# motoko_4_0.net
KiCad netlist of a schematic drawn in EAGLE
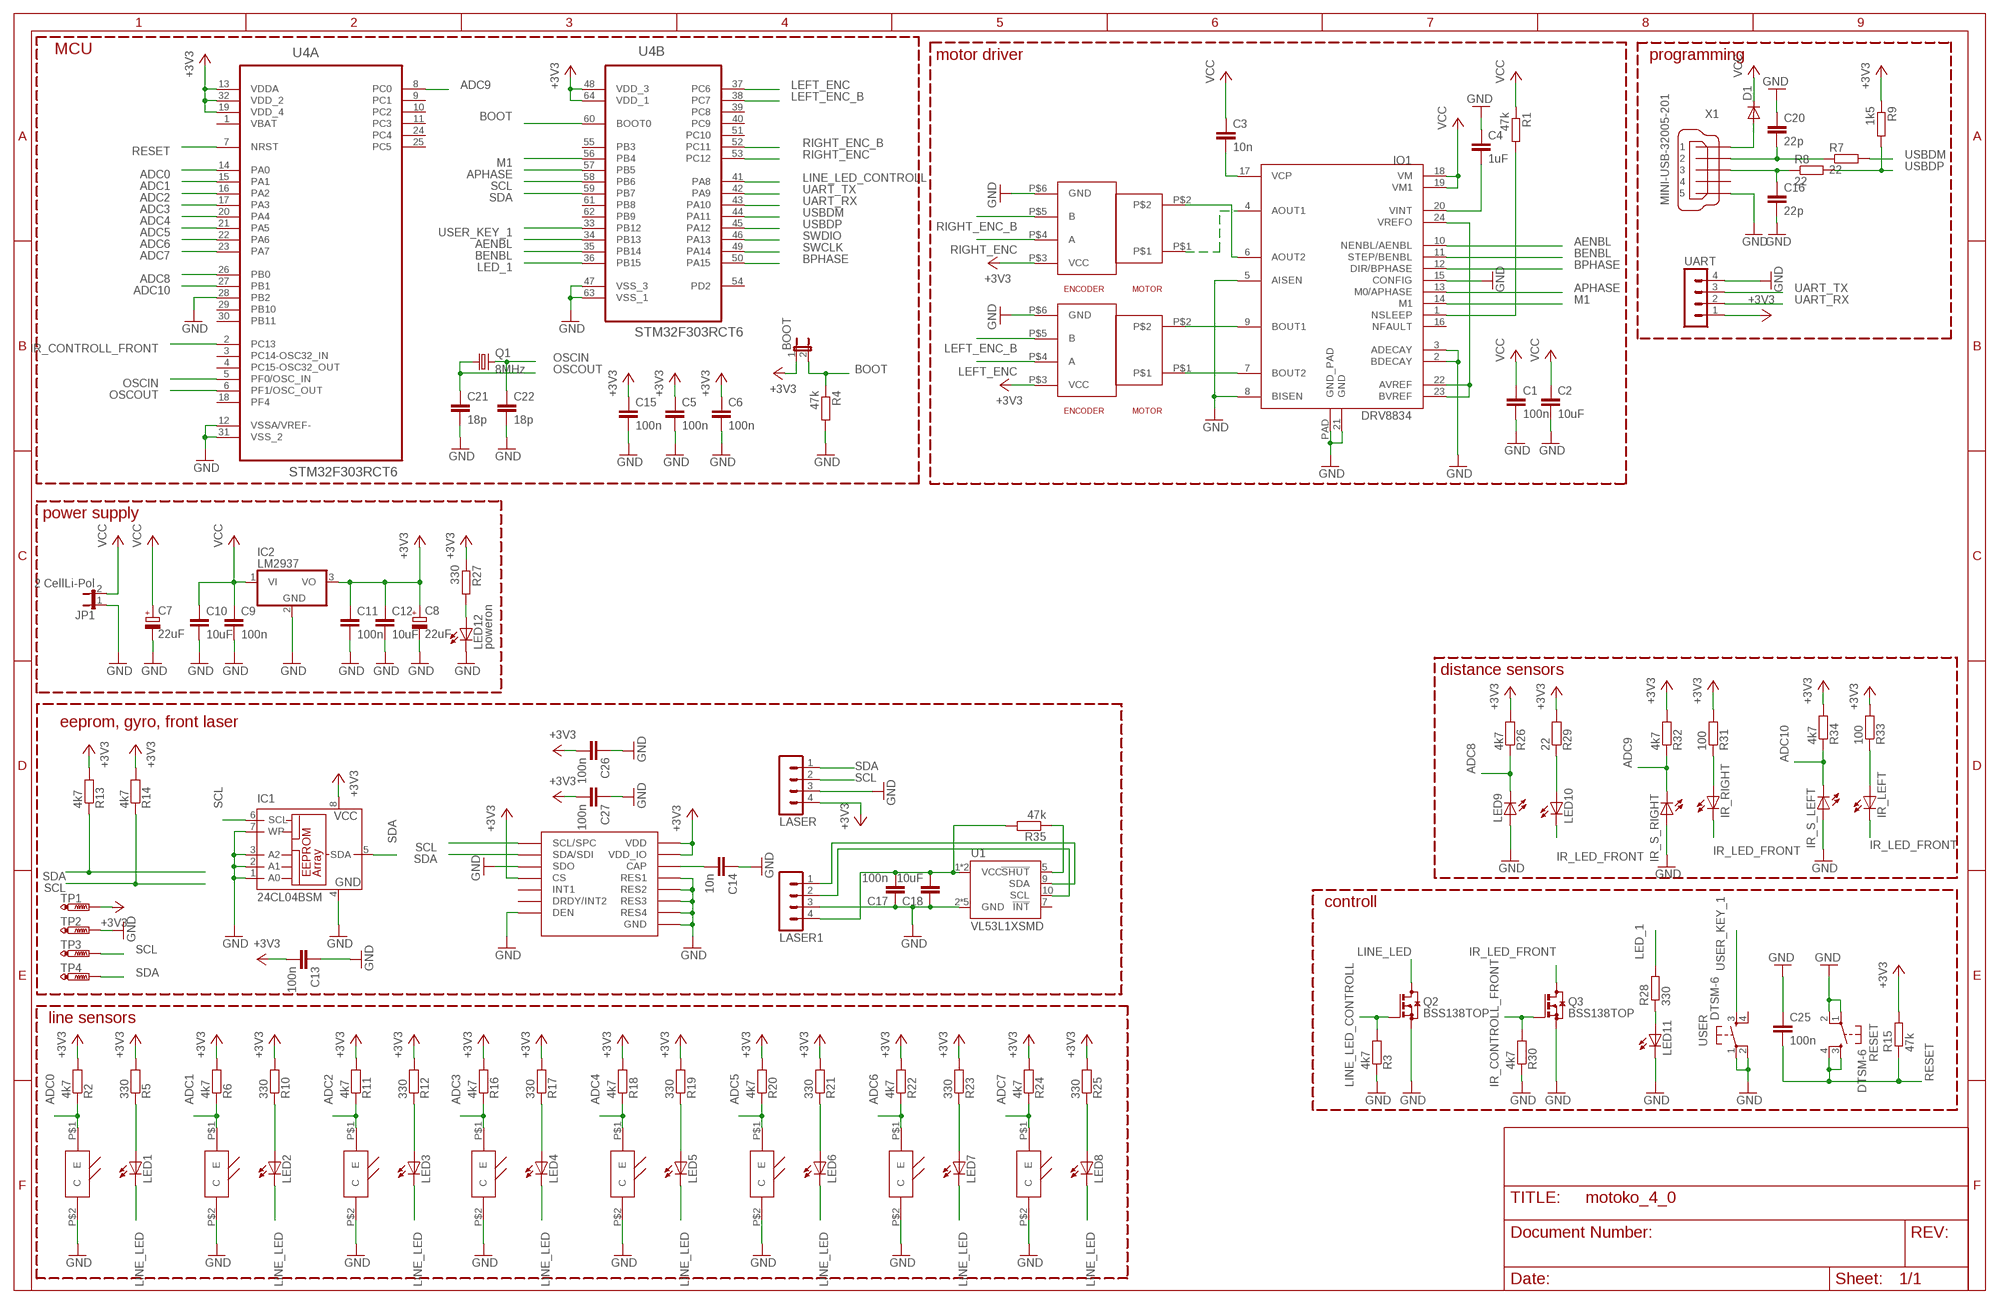
[diagram p0: schematic, sheet 1]

(export (version "E")
  (design (tool "Eeschema 10.0.6"))
  (components
    (comp (ref "BOOT")
      (value "JP1E")
      (footprint "eagle-import:JP1")
      (libsource (lib "eagle-import") (part "JP1E"))
    )
    (comp (ref "C1")
      (value "100n")
      (footprint "eagle-import:C1206")
      (libsource (lib "eagle-import") (part "C-EUC1206"))
    )
    (comp (ref "C2")
      (value "10uF")
      (footprint "eagle-import:C1206")
      (libsource (lib "eagle-import") (part "C-EUC1206"))
    )
    (comp (ref "C3")
      (value "10n")
      (footprint "eagle-import:C1206")
      (libsource (lib "eagle-import") (part "C-EUC1206"))
    )
    (comp (ref "C4")
      (value "1uF")
      (footprint "eagle-import:C1206")
      (libsource (lib "eagle-import") (part "C-EUC1206"))
    )
    (comp (ref "C5")
      (value "100n")
      (footprint "eagle-import:C0805")
      (libsource (lib "eagle-import") (part "C-EUC0805"))
    )
    (comp (ref "C6")
      (value "100n")
      (footprint "eagle-import:C0805")
      (libsource (lib "eagle-import") (part "C-EUC0805"))
    )
    (comp (ref "C7")
      (value "22uF")
      (footprint "eagle-import:153CLV-0505")
      (libsource (lib "eagle-import") (part "CPOL-EU153CLV-0505"))
    )
    (comp (ref "C8")
      (value "22uF")
      (footprint "eagle-import:153CLV-0505")
      (libsource (lib "eagle-import") (part "CPOL-EU153CLV-0505"))
    )
    (comp (ref "C9")
      (value "100n")
      (footprint "eagle-import:C0805")
      (libsource (lib "eagle-import") (part "C-EUC0805"))
    )
    (comp (ref "C10")
      (value "10uF")
      (footprint "eagle-import:C0805")
      (libsource (lib "eagle-import") (part "C-EUC0805"))
    )
    (comp (ref "C11")
      (value "100n")
      (footprint "eagle-import:C0805")
      (libsource (lib "eagle-import") (part "C-EUC0805"))
    )
    (comp (ref "C12")
      (value "10uF")
      (footprint "eagle-import:C0805")
      (libsource (lib "eagle-import") (part "C-EUC0805"))
    )
    (comp (ref "C13")
      (value "100n")
      (footprint "eagle-import:C0805")
      (libsource (lib "eagle-import") (part "C-EUC0805"))
    )
    (comp (ref "C14")
      (value "10n")
      (footprint "eagle-import:C0805")
      (libsource (lib "eagle-import") (part "C-EUC0805"))
    )
    (comp (ref "C15")
      (value "100n")
      (footprint "eagle-import:C0805")
      (libsource (lib "eagle-import") (part "C-EUC0805"))
    )
    (comp (ref "C16")
      (value "22p")
      (footprint "eagle-import:C0805")
      (libsource (lib "eagle-import") (part "C-EUC0805"))
    )
    (comp (ref "C17")
      (value "100n")
      (footprint "eagle-import:C0805")
      (libsource (lib "eagle-import") (part "C-EUC0805"))
    )
    (comp (ref "C18")
      (value "10uF")
      (footprint "eagle-import:C0805")
      (libsource (lib "eagle-import") (part "C-EUC0805"))
    )
    (comp (ref "C20")
      (value "22p")
      (footprint "eagle-import:C0805")
      (libsource (lib "eagle-import") (part "C-EUC0805"))
    )
    (comp (ref "C21")
      (value "18p")
      (footprint "eagle-import:C0805")
      (libsource (lib "eagle-import") (part "C-EUC0805"))
    )
    (comp (ref "C22")
      (value "18p")
      (footprint "eagle-import:C0805")
      (libsource (lib "eagle-import") (part "C-EUC0805"))
    )
    (comp (ref "C25")
      (value "100n")
      (footprint "eagle-import:C0805")
      (libsource (lib "eagle-import") (part "C-EUC0805"))
    )
    (comp (ref "C26")
      (value "100n")
      (footprint "eagle-import:C0805")
      (libsource (lib "eagle-import") (part "C-EUC0805"))
    )
    (comp (ref "C27")
      (value "100n")
      (footprint "eagle-import:C0805")
      (libsource (lib "eagle-import") (part "C-EUC0805"))
    )
    (comp (ref "D1")
      (value "DIODE-SMB")
      (footprint "eagle-import:SMB")
      (libsource (lib "eagle-import") (part "DIODE-SMB"))
    )
    (comp (ref "IC1")
      (value "24CL04BSM")
      (footprint "eagle-import:SO-08M")
      (fields (field (name "MPN") "FM24CL04-S"))
      (libsource (lib "eagle-import") (part "24SMCL04B"))
    )
    (comp (ref "IC2")
      (value "LM2937")
      (footprint "eagle-import:TO263-3")
      (libsource (lib "eagle-import") (part "LM2937"))
    )
    (comp (ref "IO1")
      (value "DRV8834")
      (footprint "eagle-import:DRV8834_PCK")
      (libsource (lib "eagle-import") (part "DRV8834"))
    )
    (comp (ref "IR_LEFT")
      (value "LED5MM")
      (footprint "eagle-import:LED5MM")
      (libsource (lib "eagle-import") (part "my_parts_LED5MM"))
    )
    (comp (ref "IR_RIGHT")
      (value "LED5MM")
      (footprint "eagle-import:LED5MM")
      (libsource (lib "eagle-import") (part "my_parts_LED5MM"))
    )
    (comp (ref "IR_S_LEFT")
      (value "LED5MM")
      (footprint "eagle-import:LED5MM")
      (libsource (lib "eagle-import") (part "my_parts_LED5MM"))
    )
    (comp (ref "IR_S_RIGHT")
      (value "LED5MM")
      (footprint "eagle-import:LED5MM")
      (libsource (lib "eagle-import") (part "my_parts_LED5MM"))
    )
    (comp (ref "JP1")
      (value "2 CellLi-Pol")
      (footprint "eagle-import:JP1")
      (libsource (lib "eagle-import") (part "JP1E"))
    )
    (comp (ref "LASER")
      (value "MA04-1")
      (footprint "eagle-import:MA04-1")
      (libsource (lib "eagle-import") (part "MA04-1"))
    )
    (comp (ref "LASER1")
      (value "MA04-1")
      (footprint "eagle-import:MA04-1")
      (libsource (lib "eagle-import") (part "MA04-1"))
    )
    (comp (ref "LED1")
      (value "LEDCHIPLED_1206")
      (footprint "eagle-import:CHIPLED_1206")
      (libsource (lib "eagle-import") (part "LEDCHIPLED_1206"))
    )
    (comp (ref "LED2")
      (value "LEDCHIPLED_1206")
      (footprint "eagle-import:CHIPLED_1206")
      (libsource (lib "eagle-import") (part "LEDCHIPLED_1206"))
    )
    (comp (ref "LED3")
      (value "LEDCHIPLED_1206")
      (footprint "eagle-import:CHIPLED_1206")
      (libsource (lib "eagle-import") (part "LEDCHIPLED_1206"))
    )
    (comp (ref "LED4")
      (value "LEDCHIPLED_1206")
      (footprint "eagle-import:CHIPLED_1206")
      (libsource (lib "eagle-import") (part "LEDCHIPLED_1206"))
    )
    (comp (ref "LED5")
      (value "LEDCHIPLED_1206")
      (footprint "eagle-import:CHIPLED_1206")
      (libsource (lib "eagle-import") (part "LEDCHIPLED_1206"))
    )
    (comp (ref "LED6")
      (value "LEDCHIPLED_1206")
      (footprint "eagle-import:CHIPLED_1206")
      (libsource (lib "eagle-import") (part "LEDCHIPLED_1206"))
    )
    (comp (ref "LED7")
      (value "LEDCHIPLED_1206")
      (footprint "eagle-import:CHIPLED_1206")
      (libsource (lib "eagle-import") (part "LEDCHIPLED_1206"))
    )
    (comp (ref "LED8")
      (value "LEDCHIPLED_1206")
      (footprint "eagle-import:CHIPLED_1206")
      (libsource (lib "eagle-import") (part "LEDCHIPLED_1206"))
    )
    (comp (ref "LED9")
      (value "LED5MM")
      (footprint "eagle-import:LED5MM")
      (libsource (lib "eagle-import") (part "my_parts_LED5MM"))
    )
    (comp (ref "LED10")
      (value "LED5MM")
      (footprint "eagle-import:LED5MM")
      (libsource (lib "eagle-import") (part "my_parts_LED5MM"))
    )
    (comp (ref "LED11")
      (value "LEDCHIPLED_1206")
      (footprint "eagle-import:CHIPLED_1206")
      (libsource (lib "eagle-import") (part "LEDCHIPLED_1206"))
    )
    (comp (ref "LED12")
      (value "poweron")
      (footprint "eagle-import:CHIPLED_1206")
      (libsource (lib "eagle-import") (part "LEDCHIPLED_1206"))
    )
    (comp (ref "LSM6DS0")
      (value "L3GD20H")
      (footprint "eagle-import:LGA16L")
      (libsource (lib "eagle-import") (part "L3GD20H"))
    )
    (comp (ref "Q1")
      (value "8MHz")
      (footprint "eagle-import:CTS406")
      (libsource (lib "eagle-import") (part "CRYSTALCTS406"))
    )
    (comp (ref "Q2")
      (value "BSS138TOP")
      (footprint "eagle-import:SOT23")
      (libsource (lib "eagle-import") (part "BSS138TOP"))
    )
    (comp (ref "Q3")
      (value "BSS138TOP")
      (footprint "eagle-import:SOT23")
      (libsource (lib "eagle-import") (part "BSS138TOP"))
    )
    (comp (ref "R1")
      (value "47k")
      (footprint "eagle-import:M1206")
      (libsource (lib "eagle-import") (part "R-EU_M1206"))
    )
    (comp (ref "R2")
      (value "4k7")
      (footprint "eagle-import:M0805")
      (libsource (lib "eagle-import") (part "R-EU_M0805"))
    )
    (comp (ref "R3")
      (value "4k7")
      (footprint "eagle-import:M0805")
      (libsource (lib "eagle-import") (part "R-EU_M0805"))
    )
    (comp (ref "R4")
      (value "47k")
      (footprint "eagle-import:M0805")
      (libsource (lib "eagle-import") (part "R-EU_M0805"))
    )
    (comp (ref "R5")
      (value "330")
      (footprint "eagle-import:M0805")
      (libsource (lib "eagle-import") (part "R-EU_M0805"))
    )
    (comp (ref "R6")
      (value "4k7")
      (footprint "eagle-import:M0805")
      (libsource (lib "eagle-import") (part "R-EU_M0805"))
    )
    (comp (ref "R7")
      (value "22")
      (footprint "eagle-import:M0805")
      (libsource (lib "eagle-import") (part "R-EU_M0805"))
    )
    (comp (ref "R8")
      (value "22")
      (footprint "eagle-import:M0805")
      (libsource (lib "eagle-import") (part "R-EU_M0805"))
    )
    (comp (ref "R9")
      (value "1k5")
      (footprint "eagle-import:M0805")
      (libsource (lib "eagle-import") (part "R-EU_M0805"))
    )
    (comp (ref "R10")
      (value "330")
      (footprint "eagle-import:M0805")
      (libsource (lib "eagle-import") (part "R-EU_M0805"))
    )
    (comp (ref "R11")
      (value "4k7")
      (footprint "eagle-import:M0805")
      (libsource (lib "eagle-import") (part "R-EU_M0805"))
    )
    (comp (ref "R12")
      (value "330")
      (footprint "eagle-import:M0805")
      (libsource (lib "eagle-import") (part "R-EU_M0805"))
    )
    (comp (ref "R13")
      (value "4k7")
      (footprint "eagle-import:M0805")
      (libsource (lib "eagle-import") (part "R-EU_M0805"))
    )
    (comp (ref "R14")
      (value "4k7")
      (footprint "eagle-import:M0805")
      (libsource (lib "eagle-import") (part "R-EU_M0805"))
    )
    (comp (ref "R15")
      (value "47k")
      (footprint "eagle-import:M0805")
      (libsource (lib "eagle-import") (part "R-EU_M0805"))
    )
    (comp (ref "R16")
      (value "4k7")
      (footprint "eagle-import:M0805")
      (libsource (lib "eagle-import") (part "R-EU_M0805"))
    )
    (comp (ref "R17")
      (value "330")
      (footprint "eagle-import:M0805")
      (libsource (lib "eagle-import") (part "R-EU_M0805"))
    )
    (comp (ref "R18")
      (value "4k7")
      (footprint "eagle-import:M0805")
      (libsource (lib "eagle-import") (part "R-EU_M0805"))
    )
    (comp (ref "R19")
      (value "330")
      (footprint "eagle-import:M0805")
      (libsource (lib "eagle-import") (part "R-EU_M0805"))
    )
    (comp (ref "R20")
      (value "4k7")
      (footprint "eagle-import:M0805")
      (libsource (lib "eagle-import") (part "R-EU_M0805"))
    )
    (comp (ref "R21")
      (value "330")
      (footprint "eagle-import:M0805")
      (libsource (lib "eagle-import") (part "R-EU_M0805"))
    )
    (comp (ref "R22")
      (value "4k7")
      (footprint "eagle-import:M0805")
      (libsource (lib "eagle-import") (part "R-EU_M0805"))
    )
    (comp (ref "R23")
      (value "330")
      (footprint "eagle-import:M0805")
      (libsource (lib "eagle-import") (part "R-EU_M0805"))
    )
    (comp (ref "R24")
      (value "4k7")
      (footprint "eagle-import:M0805")
      (libsource (lib "eagle-import") (part "R-EU_M0805"))
    )
    (comp (ref "R25")
      (value "330")
      (footprint "eagle-import:M0805")
      (libsource (lib "eagle-import") (part "R-EU_M0805"))
    )
    (comp (ref "R26")
      (value "4k7")
      (footprint "eagle-import:M0805")
      (libsource (lib "eagle-import") (part "R-EU_M0805"))
    )
    (comp (ref "R27")
      (value "330")
      (footprint "eagle-import:M0805")
      (libsource (lib "eagle-import") (part "R-EU_M0805"))
    )
    (comp (ref "R28")
      (value "330")
      (footprint "eagle-import:M0805")
      (libsource (lib "eagle-import") (part "R-EU_M0805"))
    )
    (comp (ref "R29")
      (value "22")
      (footprint "eagle-import:M0805")
      (libsource (lib "eagle-import") (part "R-EU_M0805"))
    )
    (comp (ref "R30")
      (value "4k7")
      (footprint "eagle-import:M0805")
      (libsource (lib "eagle-import") (part "R-EU_M0805"))
    )
    (comp (ref "R31")
      (value "100")
      (footprint "eagle-import:M0805")
      (libsource (lib "eagle-import") (part "R-EU_M0805"))
    )
    (comp (ref "R32")
      (value "4k7")
      (footprint "eagle-import:M0805")
      (libsource (lib "eagle-import") (part "R-EU_M0805"))
    )
    (comp (ref "R33")
      (value "100")
      (footprint "eagle-import:M0805")
      (libsource (lib "eagle-import") (part "R-EU_M0805"))
    )
    (comp (ref "R34")
      (value "4k7")
      (footprint "eagle-import:M0805")
      (libsource (lib "eagle-import") (part "R-EU_M0805"))
    )
    (comp (ref "R35")
      (value "47k")
      (footprint "eagle-import:M0805")
      (libsource (lib "eagle-import") (part "R-EU_M0805"))
    )
    (comp (ref "RESET")
      (value "DTSM-6")
      (footprint "eagle-import:DTSM-6")
      (libsource (lib "eagle-import") (part "DTSM-6"))
    )
    (comp (ref "TP1")
      (value "PTR1B1,27")
      (footprint "eagle-import:B1,27")
      (libsource (lib "eagle-import") (part "PTR1B1,27"))
    )
    (comp (ref "TP2")
      (value "PTR1B1,27")
      (footprint "eagle-import:B1,27")
      (libsource (lib "eagle-import") (part "PTR1B1,27"))
    )
    (comp (ref "TP3")
      (value "PTR1B1,27")
      (footprint "eagle-import:B1,27")
      (libsource (lib "eagle-import") (part "PTR1B1,27"))
    )
    (comp (ref "TP4")
      (value "PTR1B1,27")
      (footprint "eagle-import:B1,27")
      (libsource (lib "eagle-import") (part "PTR1B1,27"))
    )
    (comp (ref "U$3")
      (value "SFH3710")
      (footprint "eagle-import:SFH3710")
      (libsource (lib "eagle-import") (part "SFH3710"))
    )
    (comp (ref "U$4")
      (value "SFH3710")
      (footprint "eagle-import:SFH3710")
      (libsource (lib "eagle-import") (part "SFH3710"))
    )
    (comp (ref "U$5")
      (value "SFH3710")
      (footprint "eagle-import:SFH3710")
      (libsource (lib "eagle-import") (part "SFH3710"))
    )
    (comp (ref "U$6")
      (value "SFH3710")
      (footprint "eagle-import:SFH3710")
      (libsource (lib "eagle-import") (part "SFH3710"))
    )
    (comp (ref "U$7")
      (value "SFH3710")
      (footprint "eagle-import:SFH3710")
      (libsource (lib "eagle-import") (part "SFH3710"))
    )
    (comp (ref "U$8")
      (value "SFH3710")
      (footprint "eagle-import:SFH3710")
      (libsource (lib "eagle-import") (part "SFH3710"))
    )
    (comp (ref "U$9")
      (value "SFH3710")
      (footprint "eagle-import:SFH3710")
      (libsource (lib "eagle-import") (part "SFH3710"))
    )
    (comp (ref "U$10")
      (value "SFH3710")
      (footprint "eagle-import:SFH3710")
      (libsource (lib "eagle-import") (part "SFH3710"))
    )
    (comp (ref "U$11")
      (value "POLOLU_GEAR_MOTORPOLO")
      (footprint "eagle-import:POLOLU_GEAR_MOTOR")
      (libsource (lib "eagle-import") (part "POLOLU_GEAR_MOTORPOLO"))
    )
    (comp (ref "U$12")
      (value "POLOLU_GEAR_MOTORPOLO")
      (footprint "eagle-import:POLOLU_GEAR_MOTOR")
      (libsource (lib "eagle-import") (part "POLOLU_GEAR_MOTORPOLO"))
    )
    (comp (ref "U1")
      (value "VL53L1XSMD")
      (footprint "eagle-import:VL53L1X")
      (libsource (lib "eagle-import") (part "VL53L1XSMD"))
    )
    (comp (ref "U4")
      (value "STM32F303RCT6")
      (footprint "eagle-import:QFP50P1200X1200X160-64N")
      (libsource (lib "eagle-import") (part "STM32F303RCT6"))
    )
    (comp (ref "UART")
      (value "MA04-1")
      (footprint "eagle-import:MA04-1")
      (libsource (lib "eagle-import") (part "MA04-1"))
    )
    (comp (ref "USER")
      (value "DTSM-6")
      (footprint "eagle-import:DTSM-6")
      (libsource (lib "eagle-import") (part "DTSM-6"))
    )
    (comp (ref "X1")
      (value "MINI-USB-32005-201")
      (footprint "eagle-import:32005-201")
      (libsource (lib "eagle-import") (part "MINI-USB-32005-201"))
    )
  )
  (nets
    (net (code "1") (name "+3V3") (class "Default")
      (node (ref "BOOT") (pin "1") (pinfunction "1_1") (pintype "passive"))
      (node (ref "C11") (pin "1") (pinfunction "1_1") (pintype "passive"))
      (node (ref "C12") (pin "1") (pinfunction "1_1") (pintype "passive"))
      (node (ref "C13") (pin "2") (pinfunction "2_2") (pintype "passive"))
      (node (ref "C15") (pin "1") (pinfunction "1_1") (pintype "passive"))
      (node (ref "C26") (pin "2") (pinfunction "2_2") (pintype "passive"))
      (node (ref "C27") (pin "2") (pinfunction "2_2") (pintype "passive"))
      (node (ref "C5") (pin "1") (pinfunction "1_1") (pintype "passive"))
      (node (ref "C6") (pin "1") (pinfunction "1_1") (pintype "passive"))
      (node (ref "C8") (pin "+") (pinfunction "+_+") (pintype "passive"))
      (node (ref "IC1") (pin "8") (pinfunction "VCC_8") (pintype "power_in"))
      (node (ref "IC2") (pin "3") (pinfunction "VO_3") (pintype "passive"))
      (node (ref "LASER") (pin "4") (pinfunction "4_4") (pintype "passive"))
      (node (ref "LSM6DS0") (pin "P$1") (pinfunction "VDD_IO_P$1") (pintype "power_in"))
      (node (ref "LSM6DS0") (pin "P$16") (pinfunction "VDD_P$16") (pintype "power_in"))
      (node (ref "LSM6DS0") (pin "P$5") (pinfunction "CS_P$5") (pintype "bidirectional"))
      (node (ref "R10") (pin "2") (pinfunction "2_2") (pintype "passive"))
      (node (ref "R11") (pin "2") (pinfunction "2_2") (pintype "passive"))
      (node (ref "R12") (pin "2") (pinfunction "2_2") (pintype "passive"))
      (node (ref "R13") (pin "2") (pinfunction "2_2") (pintype "passive"))
      (node (ref "R14") (pin "2") (pinfunction "2_2") (pintype "passive"))
      (node (ref "R15") (pin "2") (pinfunction "2_2") (pintype "passive"))
      (node (ref "R16") (pin "2") (pinfunction "2_2") (pintype "passive"))
      (node (ref "R17") (pin "2") (pinfunction "2_2") (pintype "passive"))
      (node (ref "R18") (pin "2") (pinfunction "2_2") (pintype "passive"))
      (node (ref "R19") (pin "2") (pinfunction "2_2") (pintype "passive"))
      (node (ref "R2") (pin "2") (pinfunction "2_2") (pintype "passive"))
      (node (ref "R20") (pin "2") (pinfunction "2_2") (pintype "passive"))
      (node (ref "R21") (pin "2") (pinfunction "2_2") (pintype "passive"))
      (node (ref "R22") (pin "2") (pinfunction "2_2") (pintype "passive"))
      (node (ref "R23") (pin "2") (pinfunction "2_2") (pintype "passive"))
      (node (ref "R24") (pin "2") (pinfunction "2_2") (pintype "passive"))
      (node (ref "R25") (pin "2") (pinfunction "2_2") (pintype "passive"))
      (node (ref "R26") (pin "2") (pinfunction "2_2") (pintype "passive"))
      (node (ref "R27") (pin "1") (pinfunction "1_1") (pintype "passive"))
      (node (ref "R29") (pin "2") (pinfunction "2_2") (pintype "passive"))
      (node (ref "R31") (pin "2") (pinfunction "2_2") (pintype "passive"))
      (node (ref "R32") (pin "2") (pinfunction "2_2") (pintype "passive"))
      (node (ref "R33") (pin "2") (pinfunction "2_2") (pintype "passive"))
      (node (ref "R34") (pin "2") (pinfunction "2_2") (pintype "passive"))
      (node (ref "R5") (pin "2") (pinfunction "2_2") (pintype "passive"))
      (node (ref "R6") (pin "2") (pinfunction "2_2") (pintype "passive"))
      (node (ref "R9") (pin "1") (pinfunction "1_1") (pintype "passive"))
      (node (ref "TP1") (pin "TP") (pinfunction "TP_TP") (pintype "input"))
      (node (ref "U$11") (pin "P$3") (pinfunction "VCC_P$3") (pintype "bidirectional"))
      (node (ref "U$12") (pin "P$3") (pinfunction "VCC_P$3") (pintype "bidirectional"))
      (node (ref "U4") (pin "13") (pinfunction "VDDA_13") (pintype "power_in"))
      (node (ref "U4") (pin "19") (pinfunction "VDD_4_19") (pintype "power_in"))
      (node (ref "U4") (pin "32") (pinfunction "VDD_2_32") (pintype "power_in"))
      (node (ref "U4") (pin "48") (pinfunction "VDD_3_48") (pintype "power_in"))
      (node (ref "U4") (pin "64") (pinfunction "VDD_1_64") (pintype "power_in"))
      (node (ref "UART") (pin "1") (pinfunction "1_1") (pintype "passive"))
    )
    (net (code "2") (name "/ADC0") (class "Default")
      (node (ref "R2") (pin "1") (pinfunction "1_1") (pintype "passive"))
      (node (ref "U$3") (pin "P$1") (pinfunction "E_P$1") (pintype "bidirectional"))
      (node (ref "U4") (pin "14") (pinfunction "PA0_14") (pintype "bidirectional"))
    )
    (net (code "3") (name "/ADC1") (class "Default")
      (node (ref "R6") (pin "1") (pinfunction "1_1") (pintype "passive"))
      (node (ref "U$4") (pin "P$1") (pinfunction "E_P$1") (pintype "bidirectional"))
      (node (ref "U4") (pin "15") (pinfunction "PA1_15") (pintype "bidirectional"))
    )
    (net (code "4") (name "/ADC2") (class "Default")
      (node (ref "R11") (pin "1") (pinfunction "1_1") (pintype "passive"))
      (node (ref "U$5") (pin "P$1") (pinfunction "E_P$1") (pintype "bidirectional"))
      (node (ref "U4") (pin "16") (pinfunction "PA2_16") (pintype "bidirectional"))
    )
    (net (code "5") (name "/ADC3") (class "Default")
      (node (ref "R16") (pin "1") (pinfunction "1_1") (pintype "passive"))
      (node (ref "U$6") (pin "P$1") (pinfunction "E_P$1") (pintype "bidirectional"))
      (node (ref "U4") (pin "17") (pinfunction "PA3_17") (pintype "bidirectional"))
    )
    (net (code "6") (name "/ADC4") (class "Default")
      (node (ref "R18") (pin "1") (pinfunction "1_1") (pintype "passive"))
      (node (ref "U$7") (pin "P$1") (pinfunction "E_P$1") (pintype "bidirectional"))
      (node (ref "U4") (pin "20") (pinfunction "PA4_20") (pintype "bidirectional"))
    )
    (net (code "7") (name "/ADC5") (class "Default")
      (node (ref "R20") (pin "1") (pinfunction "1_1") (pintype "passive"))
      (node (ref "U$8") (pin "P$1") (pinfunction "E_P$1") (pintype "bidirectional"))
      (node (ref "U4") (pin "21") (pinfunction "PA5_21") (pintype "bidirectional"))
    )
    (net (code "8") (name "/ADC6") (class "Default")
      (node (ref "R22") (pin "1") (pinfunction "1_1") (pintype "passive"))
      (node (ref "U$9") (pin "P$1") (pinfunction "E_P$1") (pintype "bidirectional"))
      (node (ref "U4") (pin "22") (pinfunction "PA6_22") (pintype "bidirectional"))
    )
    (net (code "9") (name "/ADC7") (class "Default")
      (node (ref "R24") (pin "1") (pinfunction "1_1") (pintype "passive"))
      (node (ref "U$10") (pin "P$1") (pinfunction "E_P$1") (pintype "bidirectional"))
      (node (ref "U4") (pin "23") (pinfunction "PA7_23") (pintype "bidirectional"))
    )
    (net (code "10") (name "/ADC8") (class "Default")
      (node (ref "LED9") (pin "K") (pinfunction "C_K") (pintype "passive"))
      (node (ref "R26") (pin "1") (pinfunction "1_1") (pintype "passive"))
      (node (ref "U4") (pin "26") (pinfunction "PB0_26") (pintype "bidirectional"))
    )
    (net (code "11") (name "/ADC9") (class "Default")
      (node (ref "IR_S_RIGHT") (pin "K") (pinfunction "C_K") (pintype "passive"))
      (node (ref "R32") (pin "1") (pinfunction "1_1") (pintype "passive"))
      (node (ref "U4") (pin "8") (pinfunction "PC0_8") (pintype "bidirectional"))
    )
    (net (code "12") (name "/ADC10") (class "Default")
      (node (ref "IR_S_LEFT") (pin "K") (pinfunction "C_K") (pintype "passive"))
      (node (ref "R34") (pin "1") (pinfunction "1_1") (pintype "passive"))
      (node (ref "U4") (pin "27") (pinfunction "PB1_27") (pintype "bidirectional"))
    )
    (net (code "13") (name "/AENBL") (class "Default")
      (node (ref "IO1") (pin "10") (pinfunction "NENBL/AENBL_10") (pintype "bidirectional"))
      (node (ref "U4") (pin "34") (pinfunction "PB13_34") (pintype "bidirectional"))
    )
    (net (code "14") (name "/APHASE") (class "Default")
      (node (ref "IO1") (pin "13") (pinfunction "M0/APHASE_13") (pintype "bidirectional"))
      (node (ref "U4") (pin "57") (pinfunction "PB5_57") (pintype "bidirectional"))
    )
    (net (code "15") (name "/BENBL") (class "Default")
      (node (ref "IO1") (pin "11") (pinfunction "STEP/BENBL_11") (pintype "bidirectional"))
      (node (ref "U4") (pin "35") (pinfunction "PB14_35") (pintype "bidirectional"))
    )
    (net (code "16") (name "/BOOT") (class "Default")
      (node (ref "BOOT") (pin "2") (pinfunction "2_2") (pintype "passive"))
      (node (ref "R4") (pin "1") (pinfunction "1_1") (pintype "passive"))
      (node (ref "U4") (pin "60") (pinfunction "BOOT0_60") (pintype "input"))
    )
    (net (code "17") (name "/BPHASE") (class "Default")
      (node (ref "IO1") (pin "12") (pinfunction "DIR/BPHASE_12") (pintype "bidirectional"))
      (node (ref "U4") (pin "50") (pinfunction "PA15_50") (pintype "bidirectional"))
    )
    (net (code "18") (name "/IR_CONTROLL_FRONT") (class "Default")
      (node (ref "Q3") (pin "1") (pinfunction "G_1") (pintype "passive"))
      (node (ref "R30") (pin "2") (pinfunction "2_2") (pintype "passive"))
      (node (ref "U4") (pin "2") (pinfunction "PC13_2") (pintype "bidirectional"))
    )
    (net (code "19") (name "/IR_LED_FRONT") (class "Default")
      (node (ref "IR_LEFT") (pin "K") (pinfunction "C_K") (pintype "passive"))
      (node (ref "IR_RIGHT") (pin "K") (pinfunction "C_K") (pintype "passive"))
      (node (ref "LED10") (pin "K") (pinfunction "C_K") (pintype "passive"))
      (node (ref "Q3") (pin "3") (pinfunction "D_3") (pintype "passive"))
    )
    (net (code "20") (name "/LED_1") (class "Default")
      (node (ref "R28") (pin "2") (pinfunction "2_2") (pintype "passive"))
      (node (ref "U4") (pin "36") (pinfunction "PB15_36") (pintype "bidirectional"))
    )
    (net (code "21") (name "/LEFT_ENC") (class "Default")
      (node (ref "U$11") (pin "P$4") (pinfunction "A_P$4") (pintype "bidirectional"))
      (node (ref "U4") (pin "37") (pinfunction "PC6_37") (pintype "bidirectional"))
    )
    (net (code "22") (name "/LEFT_ENC_B") (class "Default")
      (node (ref "U$11") (pin "P$5") (pinfunction "B_P$5") (pintype "bidirectional"))
      (node (ref "U4") (pin "38") (pinfunction "PC7_38") (pintype "bidirectional"))
    )
    (net (code "23") (name "/LINE_LED") (class "Default")
      (node (ref "LED1") (pin "C") (pinfunction "C_C") (pintype "passive"))
      (node (ref "LED2") (pin "C") (pinfunction "C_C") (pintype "passive"))
      (node (ref "LED3") (pin "C") (pinfunction "C_C") (pintype "passive"))
      (node (ref "LED4") (pin "C") (pinfunction "C_C") (pintype "passive"))
      (node (ref "LED5") (pin "C") (pinfunction "C_C") (pintype "passive"))
      (node (ref "LED6") (pin "C") (pinfunction "C_C") (pintype "passive"))
      (node (ref "LED7") (pin "C") (pinfunction "C_C") (pintype "passive"))
      (node (ref "LED8") (pin "C") (pinfunction "C_C") (pintype "passive"))
      (node (ref "Q2") (pin "3") (pinfunction "D_3") (pintype "passive"))
    )
    (net (code "24") (name "/LINE_LED_CONTROLL") (class "Default")
      (node (ref "Q2") (pin "1") (pinfunction "G_1") (pintype "passive"))
      (node (ref "R3") (pin "2") (pinfunction "2_2") (pintype "passive"))
      (node (ref "U4") (pin "41") (pinfunction "PA8_41") (pintype "bidirectional"))
    )
    (net (code "25") (name "/M1") (class "Default")
      (node (ref "IO1") (pin "14") (pinfunction "M1_14") (pintype "bidirectional"))
      (node (ref "U4") (pin "56") (pinfunction "PB4_56") (pintype "bidirectional"))
    )
    (net (code "26") (name "/OSCIN") (class "Default")
      (node (ref "C22") (pin "1") (pinfunction "1_1") (pintype "passive"))
      (node (ref "Q1") (pin "3") (pinfunction "2_3") (pintype "passive"))
      (node (ref "U4") (pin "5") (pinfunction "PF0/OSC_IN_5") (pintype "bidirectional"))
    )
    (net (code "27") (name "/OSCOUT") (class "Default")
      (node (ref "C21") (pin "1") (pinfunction "1_1") (pintype "passive"))
      (node (ref "Q1") (pin "1") (pinfunction "1_1") (pintype "passive"))
      (node (ref "U4") (pin "6") (pinfunction "PF1/OSC_OUT_6") (pintype "bidirectional"))
    )
    (net (code "28") (name "/RESET") (class "Default")
      (node (ref "C25") (pin "2") (pinfunction "2_2") (pintype "passive"))
      (node (ref "R15") (pin "1") (pinfunction "1_1") (pintype "passive"))
      (node (ref "RESET") (pin "3") (pinfunction "3_3") (pintype "passive"))
      (node (ref "RESET") (pin "4") (pinfunction "4_4") (pintype "passive"))
      (node (ref "U4") (pin "7") (pinfunction "NRST_7") (pintype "bidirectional"))
    )
    (net (code "29") (name "/RIGHT_ENC") (class "Default")
      (node (ref "U$12") (pin "P$4") (pinfunction "A_P$4") (pintype "bidirectional"))
      (node (ref "U4") (pin "53") (pinfunction "PC12_53") (pintype "bidirectional"))
    )
    (net (code "30") (name "/RIGHT_ENC_B") (class "Default")
      (node (ref "U$12") (pin "P$5") (pinfunction "B_P$5") (pintype "bidirectional"))
      (node (ref "U4") (pin "52") (pinfunction "PC11_52") (pintype "bidirectional"))
    )
    (net (code "31") (name "/SCL") (class "Default")
      (node (ref "IC1") (pin "6") (pinfunction "SCL_6") (pintype "input"))
      (node (ref "LASER") (pin "2") (pinfunction "2_2") (pintype "passive"))
      (node (ref "LSM6DS0") (pin "P$2") (pinfunction "SCL/SPC_P$2") (pintype "bidirectional"))
      (node (ref "R14") (pin "1") (pinfunction "1_1") (pintype "passive"))
      (node (ref "TP3") (pin "TP") (pinfunction "TP_TP") (pintype "input"))
      (node (ref "U4") (pin "58") (pinfunction "PB6_58") (pintype "bidirectional"))
    )
    (net (code "32") (name "/SDA") (class "Default")
      (node (ref "IC1") (pin "5") (pinfunction "SDA_5") (pintype "bidirectional"))
      (node (ref "LASER") (pin "1") (pinfunction "1_1") (pintype "passive"))
      (node (ref "LSM6DS0") (pin "P$3") (pinfunction "SDA/SDI_P$3") (pintype "bidirectional"))
      (node (ref "R13") (pin "1") (pinfunction "1_1") (pintype "passive"))
      (node (ref "TP4") (pin "TP") (pinfunction "TP_TP") (pintype "input"))
      (node (ref "U4") (pin "59") (pinfunction "PB7_59") (pintype "bidirectional"))
    )
    (net (code "33") (name "/SWCLK") (class "Default")
      (node (ref "U4") (pin "49") (pinfunction "PA14_49") (pintype "bidirectional"))
    )
    (net (code "34") (name "/SWDIO") (class "Default")
      (node (ref "U4") (pin "46") (pinfunction "PA13_46") (pintype "bidirectional"))
    )
    (net (code "35") (name "/UART_RX") (class "Default")
      (node (ref "U4") (pin "43") (pinfunction "PA10_43") (pintype "bidirectional"))
      (node (ref "UART") (pin "2") (pinfunction "2_2") (pintype "passive"))
    )
    (net (code "36") (name "/UART_TX") (class "Default")
      (node (ref "U4") (pin "42") (pinfunction "PA9_42") (pintype "bidirectional"))
      (node (ref "UART") (pin "3") (pinfunction "3_3") (pintype "passive"))
    )
    (net (code "37") (name "/USBDM") (class "Default")
      (node (ref "R7") (pin "2") (pinfunction "2_2") (pintype "passive"))
      (node (ref "U4") (pin "44") (pinfunction "PA11_44") (pintype "bidirectional"))
    )
    (net (code "38") (name "/USBDP") (class "Default")
      (node (ref "R8") (pin "2") (pinfunction "2_2") (pintype "passive"))
      (node (ref "R9") (pin "2") (pinfunction "2_2") (pintype "passive"))
      (node (ref "U4") (pin "45") (pinfunction "PA12_45") (pintype "bidirectional"))
    )
    (net (code "39") (name "/USER_KEY_1") (class "Default")
      (node (ref "U4") (pin "33") (pinfunction "PB12_33") (pintype "bidirectional"))
      (node (ref "USER") (pin "3") (pinfunction "3_3") (pintype "passive"))
    )
    (net (code "40") (name "/VBAT") (class "Default")
      (node (ref "U4") (pin "1") (pinfunction "VBAT_1") (pintype "power_in"))
    )
    (net (code "41") (name "GND") (class "Default")
      (node (ref "C1") (pin "2") (pinfunction "2_2") (pintype "passive"))
      (node (ref "C10") (pin "2") (pinfunction "2_2") (pintype "passive"))
      (node (ref "C11") (pin "2") (pinfunction "2_2") (pintype "passive"))
      (node (ref "C12") (pin "2") (pinfunction "2_2") (pintype "passive"))
      (node (ref "C13") (pin "1") (pinfunction "1_1") (pintype "passive"))
      (node (ref "C14") (pin "1") (pinfunction "1_1") (pintype "passive"))
      (node (ref "C15") (pin "2") (pinfunction "2_2") (pintype "passive"))
      (node (ref "C16") (pin "2") (pinfunction "2_2") (pintype "passive"))
      (node (ref "C17") (pin "1") (pinfunction "1_1") (pintype "passive"))
      (node (ref "C18") (pin "1") (pinfunction "1_1") (pintype "passive"))
      (node (ref "C2") (pin "2") (pinfunction "2_2") (pintype "passive"))
      (node (ref "C20") (pin "1") (pinfunction "1_1") (pintype "passive"))
      (node (ref "C21") (pin "2") (pinfunction "2_2") (pintype "passive"))
      (node (ref "C22") (pin "2") (pinfunction "2_2") (pintype "passive"))
      (node (ref "C25") (pin "1") (pinfunction "1_1") (pintype "passive"))
      (node (ref "C26") (pin "1") (pinfunction "1_1") (pintype "passive"))
      (node (ref "C27") (pin "1") (pinfunction "1_1") (pintype "passive"))
      (node (ref "C4") (pin "1") (pinfunction "1_1") (pintype "passive"))
      (node (ref "C5") (pin "2") (pinfunction "2_2") (pintype "passive"))
      (node (ref "C6") (pin "2") (pinfunction "2_2") (pintype "passive"))
      (node (ref "C7") (pin "-") (pinfunction "-_-") (pintype "passive"))
      (node (ref "C8") (pin "-") (pinfunction "-_-") (pintype "passive"))
      (node (ref "C9") (pin "2") (pinfunction "2_2") (pintype "passive"))
      (node (ref "IC1") (pin "1") (pinfunction "A0_1") (pintype "input"))
      (node (ref "IC1") (pin "2") (pinfunction "A1_2") (pintype "input"))
      (node (ref "IC1") (pin "3") (pinfunction "A2_3") (pintype "input"))
      (node (ref "IC1") (pin "4") (pinfunction "GND_4") (pintype "power_in"))
      (node (ref "IC1") (pin "7") (pinfunction "WP_7") (pintype "input"))
      (node (ref "IC2") (pin "2") (pinfunction "GND_2") (pintype "passive"))
      (node (ref "IO1") (pin "15") (pinfunction "CONFIG_15") (pintype "bidirectional"))
      (node (ref "IO1") (pin "2") (pinfunction "BDECAY_2") (pintype "bidirectional"))
      (node (ref "IO1") (pin "21") (pinfunction "GND_21") (pintype "bidirectional"))
      (node (ref "IO1") (pin "3") (pinfunction "ADECAY_3") (pintype "bidirectional"))
      (node (ref "IO1") (pin "5") (pinfunction "AISEN_5") (pintype "bidirectional"))
      (node (ref "IO1") (pin "8") (pinfunction "BISEN_8") (pintype "bidirectional"))
      (node (ref "IO1") (pin "PAD") (pinfunction "GND_PAD_PAD") (pintype "bidirectional"))
      (node (ref "IR_S_LEFT") (pin "A") (pinfunction "A_A") (pintype "passive"))
      (node (ref "IR_S_RIGHT") (pin "A") (pinfunction "A_A") (pintype "passive"))
      (node (ref "JP1") (pin "1") (pinfunction "1_1") (pintype "passive"))
      (node (ref "LASER") (pin "3") (pinfunction "3_3") (pintype "passive"))
      (node (ref "LASER1") (pin "3") (pinfunction "3_3") (pintype "passive"))
      (node (ref "LED11") (pin "C") (pinfunction "C_C") (pintype "passive"))
      (node (ref "LED12") (pin "C") (pinfunction "C_C") (pintype "passive"))
      (node (ref "LED9") (pin "A") (pinfunction "A_A") (pintype "passive"))
      (node (ref "LSM6DS0") (pin "P$10") (pinfunction "RES2_P$10") (pintype "bidirectional"))
      (node (ref "LSM6DS0") (pin "P$11") (pinfunction "RES3_P$11") (pintype "bidirectional"))
      (node (ref "LSM6DS0") (pin "P$12") (pinfunction "GND_P$12") (pintype "power_in"))
      (node (ref "LSM6DS0") (pin "P$13") (pinfunction "GND_P$13") (pintype "power_in"))
      (node (ref "LSM6DS0") (pin "P$15") (pinfunction "RES4_P$15") (pintype "bidirectional"))
      (node (ref "LSM6DS0") (pin "P$4") (pinfunction "SDO_P$4") (pintype "bidirectional"))
      (node (ref "LSM6DS0") (pin "P$8") (pinfunction "DEN_P$8") (pintype "bidirectional"))
      (node (ref "LSM6DS0") (pin "P$9") (pinfunction "RES1_P$9") (pintype "bidirectional"))
      (node (ref "Q2") (pin "2") (pinfunction "S_2") (pintype "passive"))
      (node (ref "Q3") (pin "2") (pinfunction "S_2") (pintype "passive"))
      (node (ref "R3") (pin "1") (pinfunction "1_1") (pintype "passive"))
      (node (ref "R30") (pin "1") (pinfunction "1_1") (pintype "passive"))
      (node (ref "R4") (pin "2") (pinfunction "2_2") (pintype "passive"))
      (node (ref "RESET") (pin "1") (pinfunction "1_1") (pintype "passive"))
      (node (ref "RESET") (pin "2") (pinfunction "2_2") (pintype "passive"))
      (node (ref "TP2") (pin "TP") (pinfunction "TP_TP") (pintype "input"))
      (node (ref "U$10") (pin "P$2") (pinfunction "C_P$2") (pintype "bidirectional"))
      (node (ref "U$11") (pin "P$6") (pinfunction "GND_P$6") (pintype "bidirectional"))
      (node (ref "U$12") (pin "P$6") (pinfunction "GND_P$6") (pintype "bidirectional"))
      (node (ref "U$3") (pin "P$2") (pinfunction "C_P$2") (pintype "bidirectional"))
      (node (ref "U$4") (pin "P$2") (pinfunction "C_P$2") (pintype "bidirectional"))
      (node (ref "U$5") (pin "P$2") (pinfunction "C_P$2") (pintype "bidirectional"))
      (node (ref "U$6") (pin "P$2") (pinfunction "C_P$2") (pintype "bidirectional"))
      (node (ref "U$7") (pin "P$2") (pinfunction "C_P$2") (pintype "bidirectional"))
      (node (ref "U$8") (pin "P$2") (pinfunction "C_P$2") (pintype "bidirectional"))
      (node (ref "U$9") (pin "P$2") (pinfunction "C_P$2") (pintype "bidirectional"))
      (node (ref "U1") (pin "12") (pinfunction "GND_12") (pintype "bidirectional"))
      (node (ref "U1") (pin "2") (pinfunction "GND_2") (pintype "bidirectional"))
      (node (ref "U1") (pin "3") (pinfunction "GND_3") (pintype "bidirectional"))
      (node (ref "U1") (pin "4") (pinfunction "GND_4") (pintype "bidirectional"))
      (node (ref "U1") (pin "6") (pinfunction "GND_6") (pintype "bidirectional"))
      (node (ref "U4") (pin "12") (pinfunction "VSSA/VREF-_12") (pintype "power_in"))
      (node (ref "U4") (pin "28") (pinfunction "PB2_28") (pintype "bidirectional"))
      (node (ref "U4") (pin "31") (pinfunction "VSS_2_31") (pintype "passive"))
      (node (ref "U4") (pin "47") (pinfunction "VSS_3_47") (pintype "passive"))
      (node (ref "U4") (pin "63") (pinfunction "VSS_1_63") (pintype "passive"))
      (node (ref "UART") (pin "4") (pinfunction "4_4") (pintype "passive"))
      (node (ref "USER") (pin "1") (pinfunction "1_1") (pintype "passive"))
      (node (ref "USER") (pin "2") (pinfunction "2_2") (pintype "passive"))
      (node (ref "X1") (pin "5") (pinfunction "5_5") (pintype "passive"))
    )
    (net (code "42") (name "Net-(C16-Pad1)") (class "Default")
      (node (ref "C16") (pin "1") (pinfunction "1_1") (pintype "passive"))
      (node (ref "R8") (pin "1") (pinfunction "1_1") (pintype "passive"))
      (node (ref "X1") (pin "3") (pinfunction "3_3") (pintype "passive"))
    )
    (net (code "43") (name "Net-(C17-Pad2)") (class "Default")
      (node (ref "C17") (pin "2") (pinfunction "2_2") (pintype "passive"))
      (node (ref "C18") (pin "2") (pinfunction "2_2") (pintype "passive"))
      (node (ref "LASER1") (pin "4") (pinfunction "4_4") (pintype "passive"))
      (node (ref "R35") (pin "2") (pinfunction "2_2") (pintype "passive"))
      (node (ref "U1") (pin "1") (pinfunction "VCC_1") (pintype "bidirectional"))
      (node (ref "U1") (pin "11") (pinfunction "VCC_11") (pintype "bidirectional"))
    )
    (net (code "44") (name "Net-(C20-Pad2)") (class "Default")
      (node (ref "C20") (pin "2") (pinfunction "2_2") (pintype "passive"))
      (node (ref "R7") (pin "1") (pinfunction "1_1") (pintype "passive"))
      (node (ref "X1") (pin "2") (pinfunction "2_2") (pintype "passive"))
    )
    (net (code "45") (name "Net-(D1-PadA)") (class "Default")
      (node (ref "D1") (pin "A") (pinfunction "A_A") (pintype "passive"))
      (node (ref "X1") (pin "1") (pinfunction "1_1") (pintype "passive"))
    )
    (net (code "46") (name "Net-(IO1-AOUT1)") (class "Default")
      (node (ref "IO1") (pin "4") (pinfunction "AOUT1_4") (pintype "bidirectional"))
      (node (ref "U$12") (pin "P$1") (pinfunction "P$1_P$1") (pintype "bidirectional"))
    )
    (net (code "47") (name "Net-(IO1-AOUT2)") (class "Default")
      (node (ref "IO1") (pin "6") (pinfunction "AOUT2_6") (pintype "bidirectional"))
      (node (ref "U$12") (pin "P$2") (pinfunction "P$2_P$2") (pintype "bidirectional"))
    )
    (net (code "48") (name "Net-(IO1-AVREF)") (class "Default")
      (node (ref "IO1") (pin "22") (pinfunction "AVREF_22") (pintype "bidirectional"))
      (node (ref "IO1") (pin "23") (pinfunction "BVREF_23") (pintype "bidirectional"))
      (node (ref "IO1") (pin "24") (pinfunction "VREFO_24") (pintype "bidirectional"))
    )
    (net (code "49") (name "Net-(IO1-BOUT1)") (class "Default")
      (node (ref "IO1") (pin "9") (pinfunction "BOUT1_9") (pintype "bidirectional"))
      (node (ref "U$11") (pin "P$2") (pinfunction "P$2_P$2") (pintype "bidirectional"))
    )
    (net (code "50") (name "Net-(IO1-BOUT2)") (class "Default")
      (node (ref "IO1") (pin "7") (pinfunction "BOUT2_7") (pintype "bidirectional"))
      (node (ref "U$11") (pin "P$1") (pinfunction "P$1_P$1") (pintype "bidirectional"))
    )
    (net (code "51") (name "Net-(IO1-NSLEEP)") (class "Default")
      (node (ref "IO1") (pin "1") (pinfunction "NSLEEP_1") (pintype "bidirectional"))
      (node (ref "R1") (pin "2") (pinfunction "2_2") (pintype "passive"))
    )
    (net (code "52") (name "Net-(IO1-VCP)") (class "Default")
      (node (ref "C3") (pin "2") (pinfunction "2_2") (pintype "passive"))
      (node (ref "IO1") (pin "17") (pinfunction "VCP_17") (pintype "bidirectional"))
    )
    (net (code "53") (name "Net-(IO1-VINT)") (class "Default")
      (node (ref "C4") (pin "2") (pinfunction "2_2") (pintype "passive"))
      (node (ref "IO1") (pin "20") (pinfunction "VINT_20") (pintype "bidirectional"))
    )
    (net (code "54") (name "Net-(IR_LEFT-PadA)") (class "Default")
      (node (ref "IR_LEFT") (pin "A") (pinfunction "A_A") (pintype "passive"))
      (node (ref "R33") (pin "1") (pinfunction "1_1") (pintype "passive"))
    )
    (net (code "55") (name "Net-(IR_RIGHT-PadA)") (class "Default")
      (node (ref "IR_RIGHT") (pin "A") (pinfunction "A_A") (pintype "passive"))
      (node (ref "R31") (pin "1") (pinfunction "1_1") (pintype "passive"))
    )
    (net (code "56") (name "Net-(LED1-PadA)") (class "Default")
      (node (ref "LED1") (pin "A") (pinfunction "A_A") (pintype "passive"))
      (node (ref "R5") (pin "1") (pinfunction "1_1") (pintype "passive"))
    )
    (net (code "57") (name "Net-(LED2-PadA)") (class "Default")
      (node (ref "LED2") (pin "A") (pinfunction "A_A") (pintype "passive"))
      (node (ref "R10") (pin "1") (pinfunction "1_1") (pintype "passive"))
    )
    (net (code "58") (name "Net-(LED3-PadA)") (class "Default")
      (node (ref "LED3") (pin "A") (pinfunction "A_A") (pintype "passive"))
      (node (ref "R12") (pin "1") (pinfunction "1_1") (pintype "passive"))
    )
    (net (code "59") (name "Net-(LED4-PadA)") (class "Default")
      (node (ref "LED4") (pin "A") (pinfunction "A_A") (pintype "passive"))
      (node (ref "R17") (pin "1") (pinfunction "1_1") (pintype "passive"))
    )
    (net (code "60") (name "Net-(LED5-PadA)") (class "Default")
      (node (ref "LED5") (pin "A") (pinfunction "A_A") (pintype "passive"))
      (node (ref "R19") (pin "1") (pinfunction "1_1") (pintype "passive"))
    )
    (net (code "61") (name "Net-(LED6-PadA)") (class "Default")
      (node (ref "LED6") (pin "A") (pinfunction "A_A") (pintype "passive"))
      (node (ref "R21") (pin "1") (pinfunction "1_1") (pintype "passive"))
    )
    (net (code "62") (name "Net-(LED7-PadA)") (class "Default")
      (node (ref "LED7") (pin "A") (pinfunction "A_A") (pintype "passive"))
      (node (ref "R23") (pin "1") (pinfunction "1_1") (pintype "passive"))
    )
    (net (code "63") (name "Net-(LED8-PadA)") (class "Default")
      (node (ref "LED8") (pin "A") (pinfunction "A_A") (pintype "passive"))
      (node (ref "R25") (pin "1") (pinfunction "1_1") (pintype "passive"))
    )
    (net (code "64") (name "Net-(LED10-PadA)") (class "Default")
      (node (ref "LED10") (pin "A") (pinfunction "A_A") (pintype "passive"))
      (node (ref "R29") (pin "1") (pinfunction "1_1") (pintype "passive"))
    )
    (net (code "65") (name "Net-(LED11-PadA)") (class "Default")
      (node (ref "LED11") (pin "A") (pinfunction "A_A") (pintype "passive"))
      (node (ref "R28") (pin "1") (pinfunction "1_1") (pintype "passive"))
    )
    (net (code "66") (name "Net-(LED12-PadA)") (class "Default")
      (node (ref "LED12") (pin "A") (pinfunction "A_A") (pintype "passive"))
      (node (ref "R27") (pin "2") (pinfunction "2_2") (pintype "passive"))
    )
    (net (code "67") (name "Net-(LSM6DS0-CAP)") (class "Default")
      (node (ref "C14") (pin "2") (pinfunction "2_2") (pintype "passive"))
      (node (ref "LSM6DS0") (pin "P$14") (pinfunction "CAP_P$14") (pintype "bidirectional"))
    )
    (net (code "68") (name "Net-(U1-SCL)") (class "Default")
      (node (ref "LASER1") (pin "2") (pinfunction "2_2") (pintype "passive"))
      (node (ref "U1") (pin "10") (pinfunction "SCL_10") (pintype "bidirectional"))
    )
    (net (code "69") (name "Net-(U1-SDA)") (class "Default")
      (node (ref "LASER1") (pin "1") (pinfunction "1_1") (pintype "passive"))
      (node (ref "U1") (pin "9") (pinfunction "SDA_9") (pintype "bidirectional"))
    )
    (net (code "70") (name "Net-(U1-~{SHUT})") (class "Default")
      (node (ref "R35") (pin "1") (pinfunction "1_1") (pintype "passive"))
      (node (ref "U1") (pin "5") (pinfunction "~{SHUT}_5") (pintype "bidirectional"))
    )
    (net (code "71") (name "VCC") (class "Default")
      (node (ref "C1") (pin "1") (pinfunction "1_1") (pintype "passive"))
      (node (ref "C10") (pin "1") (pinfunction "1_1") (pintype "passive"))
      (node (ref "C2") (pin "1") (pinfunction "1_1") (pintype "passive"))
      (node (ref "C3") (pin "1") (pinfunction "1_1") (pintype "passive"))
      (node (ref "C7") (pin "+") (pinfunction "+_+") (pintype "passive"))
      (node (ref "C9") (pin "1") (pinfunction "1_1") (pintype "passive"))
      (node (ref "D1") (pin "C") (pinfunction "C_C") (pintype "passive"))
      (node (ref "IC2") (pin "1") (pinfunction "VI_1") (pintype "input"))
      (node (ref "IO1") (pin "18") (pinfunction "VM_18") (pintype "bidirectional"))
      (node (ref "IO1") (pin "19") (pinfunction "VM1_19") (pintype "bidirectional"))
      (node (ref "JP1") (pin "2") (pinfunction "2_2") (pintype "passive"))
      (node (ref "R1") (pin "1") (pinfunction "1_1") (pintype "passive"))
    )
    (net (code "72") (name "unconnected-(IO1-NFAULT-Pad16)") (class "Default")
      (node (ref "IO1") (pin "16") (pinfunction "NFAULT_16") (pintype "bidirectional"))
    )
    (net (code "73") (name "unconnected-(LSM6DS0-DRDY{slash}INT2-PadP$6)") (class "Default")
      (node (ref "LSM6DS0") (pin "P$6") (pinfunction "DRDY/INT2_P$6") (pintype "bidirectional"))
    )
    (net (code "74") (name "unconnected-(LSM6DS0-INT1-PadP$7)") (class "Default")
      (node (ref "LSM6DS0") (pin "P$7") (pinfunction "INT1_P$7") (pintype "bidirectional"))
    )
    (net (code "75") (name "unconnected-(U1-~{INT}-Pad7)") (class "Default")
      (node (ref "U1") (pin "7") (pinfunction "~{INT}_7") (pintype "bidirectional"))
    )
    (net (code "76") (name "unconnected-(U4A-PB10-Pad29)") (class "Default")
      (node (ref "U4") (pin "29") (pinfunction "PB10_29") (pintype "bidirectional"))
    )
    (net (code "77") (name "unconnected-(U4A-PB11-Pad30)") (class "Default")
      (node (ref "U4") (pin "30") (pinfunction "PB11_30") (pintype "bidirectional"))
    )
    (net (code "78") (name "unconnected-(U4A-PC1-Pad9)") (class "Default")
      (node (ref "U4") (pin "9") (pinfunction "PC1_9") (pintype "bidirectional"))
    )
    (net (code "79") (name "unconnected-(U4A-PC2-Pad10)") (class "Default")
      (node (ref "U4") (pin "10") (pinfunction "PC2_10") (pintype "bidirectional"))
    )
    (net (code "80") (name "unconnected-(U4A-PC3-Pad11)") (class "Default")
      (node (ref "U4") (pin "11") (pinfunction "PC3_11") (pintype "bidirectional"))
    )
    (net (code "81") (name "unconnected-(U4A-PC4-Pad24)") (class "Default")
      (node (ref "U4") (pin "24") (pinfunction "PC4_24") (pintype "bidirectional"))
    )
    (net (code "82") (name "unconnected-(U4A-PC5-Pad25)") (class "Default")
      (node (ref "U4") (pin "25") (pinfunction "PC5_25") (pintype "bidirectional"))
    )
    (net (code "83") (name "unconnected-(U4A-PC14-OSC32_IN-Pad3)") (class "Default")
      (node (ref "U4") (pin "3") (pinfunction "PC14-OSC32_IN_3") (pintype "bidirectional"))
    )
    (net (code "84") (name "unconnected-(U4A-PC15-OSC32_OUT-Pad4)") (class "Default")
      (node (ref "U4") (pin "4") (pinfunction "PC15-OSC32_OUT_4") (pintype "bidirectional"))
    )
    (net (code "85") (name "unconnected-(U4A-PF4-Pad18)") (class "Default")
      (node (ref "U4") (pin "18") (pinfunction "PF4_18") (pintype "bidirectional"))
    )
    (net (code "86") (name "unconnected-(U4B-PB3-Pad55)") (class "Default")
      (node (ref "U4") (pin "55") (pinfunction "PB3_55") (pintype "bidirectional"))
    )
    (net (code "87") (name "unconnected-(U4B-PB8-Pad61)") (class "Default")
      (node (ref "U4") (pin "61") (pinfunction "PB8_61") (pintype "bidirectional"))
    )
    (net (code "88") (name "unconnected-(U4B-PB9-Pad62)") (class "Default")
      (node (ref "U4") (pin "62") (pinfunction "PB9_62") (pintype "bidirectional"))
    )
    (net (code "89") (name "unconnected-(U4B-PC8-Pad39)") (class "Default")
      (node (ref "U4") (pin "39") (pinfunction "PC8_39") (pintype "bidirectional"))
    )
    (net (code "90") (name "unconnected-(U4B-PC9-Pad40)") (class "Default")
      (node (ref "U4") (pin "40") (pinfunction "PC9_40") (pintype "bidirectional"))
    )
    (net (code "91") (name "unconnected-(U4B-PC10-Pad51)") (class "Default")
      (node (ref "U4") (pin "51") (pinfunction "PC10_51") (pintype "bidirectional"))
    )
    (net (code "92") (name "unconnected-(U4B-PD2-Pad54)") (class "Default")
      (node (ref "U4") (pin "54") (pinfunction "PD2_54") (pintype "bidirectional"))
    )
    (net (code "93") (name "unconnected-(USER-Pad4)") (class "Default")
      (node (ref "USER") (pin "4") (pinfunction "4_4") (pintype "passive"))
    )
    (net (code "94") (name "unconnected-(X1-Pad4)") (class "Default")
      (node (ref "X1") (pin "4") (pinfunction "4_4") (pintype "passive"))
    )
  )
)
